# control_bdr.net
KiCad netlist of a schematic drawn in EAGLE
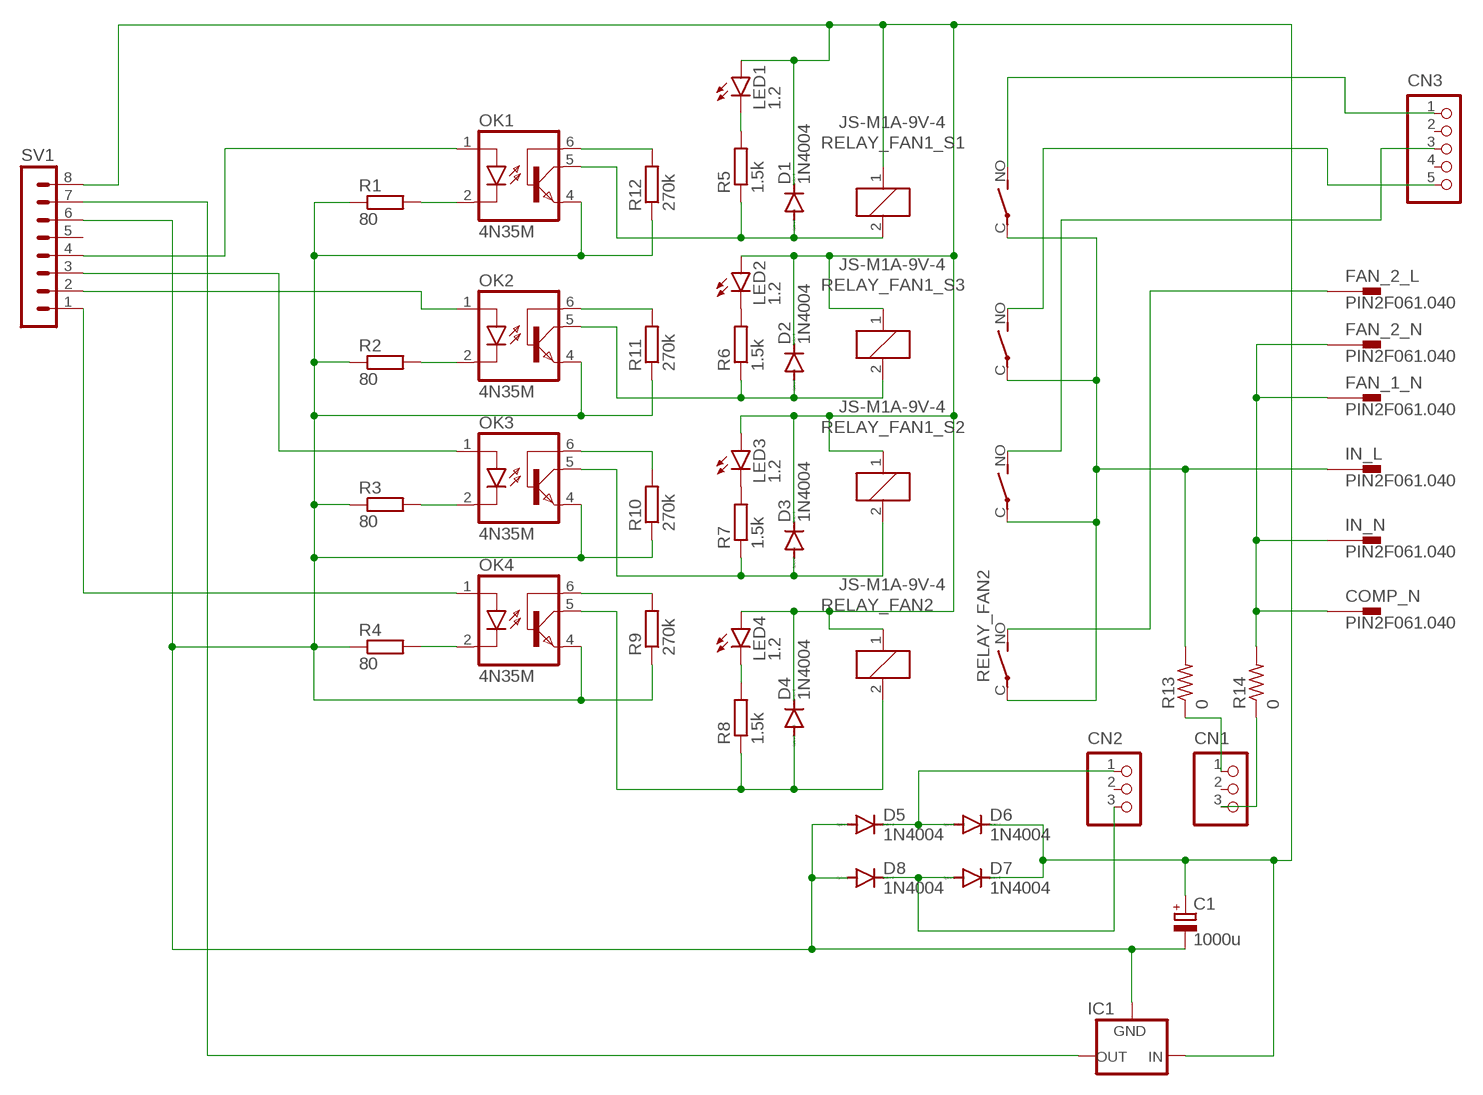
[diagram p0: schematic, sheet 1]

(export (version "E")
  (design (tool "Eeschema 10.0.6"))
  (components
    (comp (ref "C1")
      (value "1000u")
      (footprint "eagle-import:E3,5-10")
      (libsource (lib "eagle-import") (part "CPOL-EUE3.5-10"))
    )
    (comp (ref "CN1")
      (value "B3P-VH")
      (footprint "eagle-import:B3P-VH")
      (libsource (lib "eagle-import") (part "B3P-VH"))
    )
    (comp (ref "CN2")
      (value "B3B-XASK-1")
      (footprint "eagle-import:B3B-XASK-1")
      (libsource (lib "eagle-import") (part "B3B-XASK-1"))
    )
    (comp (ref "CN3")
      (value "B5P-VH")
      (footprint "eagle-import:B5P-VH")
      (libsource (lib "eagle-import") (part "B5P-VH"))
    )
    (comp (ref "COMP_N")
      (value "PIN2F061.040")
      (footprint "eagle-import:F061.040")
      (libsource (lib "eagle-import") (part "PIN2F061.040"))
    )
    (comp (ref "D1")
      (value "1N4004")
      (footprint "eagle-import:DO41-10")
      (libsource (lib "eagle-import") (part "1N4004"))
    )
    (comp (ref "D2")
      (value "1N4004")
      (footprint "eagle-import:DO41-10")
      (libsource (lib "eagle-import") (part "1N4004"))
    )
    (comp (ref "D3")
      (value "1N4004")
      (footprint "eagle-import:DO41-10")
      (libsource (lib "eagle-import") (part "1N4004"))
    )
    (comp (ref "D4")
      (value "1N4004")
      (footprint "eagle-import:DO41-10")
      (libsource (lib "eagle-import") (part "1N4004"))
    )
    (comp (ref "D5")
      (value "1N4004")
      (footprint "eagle-import:DO41-10")
      (libsource (lib "eagle-import") (part "1N4004"))
    )
    (comp (ref "D6")
      (value "1N4004")
      (footprint "eagle-import:DO41-10")
      (libsource (lib "eagle-import") (part "1N4004"))
    )
    (comp (ref "D7")
      (value "1N4004")
      (footprint "eagle-import:DO41-10")
      (libsource (lib "eagle-import") (part "1N4004"))
    )
    (comp (ref "D8")
      (value "1N4004")
      (footprint "eagle-import:DO41-10")
      (libsource (lib "eagle-import") (part "1N4004"))
    )
    (comp (ref "FAN_1_N")
      (value "PIN2F061.040")
      (footprint "eagle-import:F061.040")
      (libsource (lib "eagle-import") (part "PIN2F061.040"))
    )
    (comp (ref "FAN_2_L")
      (value "PIN2F061.040")
      (footprint "eagle-import:F061.040")
      (libsource (lib "eagle-import") (part "PIN2F061.040"))
    )
    (comp (ref "FAN_2_N")
      (value "PIN2F061.040")
      (footprint "eagle-import:F061.040")
      (libsource (lib "eagle-import") (part "PIN2F061.040"))
    )
    (comp (ref "IC1")
      (value "78XXL")
      (footprint "eagle-import:78XXL")
      (libsource (lib "eagle-import") (part "78XXL"))
    )
    (comp (ref "IN_L")
      (value "PIN2F061.040")
      (footprint "eagle-import:F061.040")
      (libsource (lib "eagle-import") (part "PIN2F061.040"))
    )
    (comp (ref "IN_N")
      (value "PIN2F061.040")
      (footprint "eagle-import:F061.040")
      (libsource (lib "eagle-import") (part "PIN2F061.040"))
    )
    (comp (ref "LED1")
      (value "1.2")
      (footprint "eagle-import:LED5MM")
      (libsource (lib "eagle-import") (part "LED5MM"))
    )
    (comp (ref "LED2")
      (value "1.2")
      (footprint "eagle-import:LED5MM")
      (libsource (lib "eagle-import") (part "LED5MM"))
    )
    (comp (ref "LED3")
      (value "1.2")
      (footprint "eagle-import:LED5MM")
      (libsource (lib "eagle-import") (part "LED5MM"))
    )
    (comp (ref "LED4")
      (value "1.2")
      (footprint "eagle-import:LED5MM")
      (libsource (lib "eagle-import") (part "LED5MM"))
    )
    (comp (ref "OK1")
      (value "4N35M")
      (footprint "eagle-import:DIL06")
      (fields (field (name "MPN") "4N35-M"))
      (libsource (lib "eagle-import") (part "4N?M35"))
    )
    (comp (ref "OK2")
      (value "4N35M")
      (footprint "eagle-import:DIL06")
      (fields (field (name "MPN") "4N35-M"))
      (libsource (lib "eagle-import") (part "4N?M35"))
    )
    (comp (ref "OK3")
      (value "4N35M")
      (footprint "eagle-import:DIL06")
      (fields (field (name "MPN") "4N35-M"))
      (libsource (lib "eagle-import") (part "4N?M35"))
    )
    (comp (ref "OK4")
      (value "4N35M")
      (footprint "eagle-import:DIL06")
      (fields (field (name "MPN") "4N35-M"))
      (libsource (lib "eagle-import") (part "4N?M35"))
    )
    (comp (ref "R1")
      (value "80")
      (footprint "eagle-import:0204_7")
      (libsource (lib "eagle-import") (part "R-EU_0204/7"))
    )
    (comp (ref "R2")
      (value "80")
      (footprint "eagle-import:0204_7")
      (libsource (lib "eagle-import") (part "R-EU_0204/7"))
    )
    (comp (ref "R3")
      (value "80")
      (footprint "eagle-import:0204_7")
      (libsource (lib "eagle-import") (part "R-EU_0204/7"))
    )
    (comp (ref "R4")
      (value "80")
      (footprint "eagle-import:0204_7")
      (libsource (lib "eagle-import") (part "R-EU_0204/7"))
    )
    (comp (ref "R5")
      (value "1.5k")
      (footprint "eagle-import:0204_7")
      (libsource (lib "eagle-import") (part "R-EU_0204/7"))
    )
    (comp (ref "R6")
      (value "1.5k")
      (footprint "eagle-import:0204_7")
      (libsource (lib "eagle-import") (part "R-EU_0204/7"))
    )
    (comp (ref "R7")
      (value "1.5k")
      (footprint "eagle-import:0204_7")
      (libsource (lib "eagle-import") (part "R-EU_0204/7"))
    )
    (comp (ref "R8")
      (value "1.5k")
      (footprint "eagle-import:0204_7")
      (libsource (lib "eagle-import") (part "R-EU_0204/7"))
    )
    (comp (ref "R9")
      (value "270k")
      (footprint "eagle-import:0204_7")
      (libsource (lib "eagle-import") (part "R-EU_0204/7"))
    )
    (comp (ref "R10")
      (value "270k")
      (footprint "eagle-import:0204_7")
      (libsource (lib "eagle-import") (part "R-EU_0204/7"))
    )
    (comp (ref "R11")
      (value "270k")
      (footprint "eagle-import:0204_7")
      (libsource (lib "eagle-import") (part "R-EU_0204/7"))
    )
    (comp (ref "R12")
      (value "270k")
      (footprint "eagle-import:0204_7")
      (libsource (lib "eagle-import") (part "R-EU_0204/7"))
    )
    (comp (ref "R13")
      (value "0")
      (footprint "eagle-import:0204V")
      (libsource (lib "eagle-import") (part "R-US_0204/2V"))
    )
    (comp (ref "R14")
      (value "0")
      (footprint "eagle-import:0204V")
      (libsource (lib "eagle-import") (part "R-US_0204/2V"))
    )
    (comp (ref "RELAY_FAN1_S1")
      (value "JS-M1A-9V-4")
      (footprint "eagle-import:JS-M1A")
      (libsource (lib "eagle-import") (part "JS-M1A-9V-4"))
    )
    (comp (ref "RELAY_FAN1_S2")
      (value "JS-M1A-9V-4")
      (footprint "eagle-import:JS-M1A")
      (libsource (lib "eagle-import") (part "JS-M1A-9V-4"))
    )
    (comp (ref "RELAY_FAN1_S3")
      (value "JS-M1A-9V-4")
      (footprint "eagle-import:JS-M1A")
      (libsource (lib "eagle-import") (part "JS-M1A-9V-4"))
    )
    (comp (ref "RELAY_FAN2")
      (value "JS-M1A-9V-4")
      (footprint "eagle-import:JS-M1A")
      (libsource (lib "eagle-import") (part "JS-M1A-9V-4"))
    )
    (comp (ref "SV1")
      (value "MA08-1")
      (footprint "eagle-import:MA08-1")
      (libsource (lib "eagle-import") (part "MA08-1"))
    )
  )
  (nets
    (net (code "1") (name "Net-(C1-Pad+)") (class "Default")
      (node (ref "C1") (pin "+") (pinfunction "+_+") (pintype "passive"))
      (node (ref "D1") (pin "C") (pinfunction "C_C") (pintype "passive"))
      (node (ref "D2") (pin "C") (pinfunction "C_C") (pintype "passive"))
      (node (ref "D3") (pin "C") (pinfunction "C_C") (pintype "passive"))
      (node (ref "D4") (pin "C") (pinfunction "C_C") (pintype "passive"))
      (node (ref "D6") (pin "C") (pinfunction "C_C") (pintype "passive"))
      (node (ref "D7") (pin "C") (pinfunction "C_C") (pintype "passive"))
      (node (ref "IC1") (pin "IN") (pinfunction "IN_IN") (pintype "input"))
      (node (ref "LED1") (pin "A") (pinfunction "A_A") (pintype "passive"))
      (node (ref "LED2") (pin "A") (pinfunction "A_A") (pintype "passive"))
      (node (ref "LED3") (pin "A") (pinfunction "A_A") (pintype "passive"))
      (node (ref "LED4") (pin "A") (pinfunction "A_A") (pintype "passive"))
      (node (ref "RELAY_FAN1_S1") (pin "1") (pinfunction "1_1") (pintype "passive"))
      (node (ref "RELAY_FAN1_S2") (pin "1") (pinfunction "1_1") (pintype "passive"))
      (node (ref "RELAY_FAN1_S3") (pin "1") (pinfunction "1_1") (pintype "passive"))
      (node (ref "RELAY_FAN2") (pin "1") (pinfunction "1_1") (pintype "passive"))
      (node (ref "SV1") (pin "8") (pinfunction "8_8") (pintype "passive"))
    )
    (net (code "2") (name "Net-(CN1-Pad1)") (class "Default")
      (node (ref "CN1") (pin "1") (pinfunction "1_1") (pintype "passive"))
      (node (ref "R13") (pin "1") (pinfunction "1_1") (pintype "passive"))
    )
    (net (code "3") (name "Net-(CN1-Pad3)") (class "Default")
      (node (ref "CN1") (pin "3") (pinfunction "3_3") (pintype "passive"))
      (node (ref "R14") (pin "1") (pinfunction "1_1") (pintype "passive"))
    )
    (net (code "4") (name "Net-(CN2-Pad1)") (class "Default")
      (node (ref "CN2") (pin "1") (pinfunction "1_1") (pintype "passive"))
      (node (ref "D5") (pin "C") (pinfunction "C_C") (pintype "passive"))
      (node (ref "D6") (pin "A") (pinfunction "A_A") (pintype "passive"))
    )
    (net (code "5") (name "Net-(CN2-Pad3)") (class "Default")
      (node (ref "CN2") (pin "3") (pinfunction "3_3") (pintype "passive"))
      (node (ref "D7") (pin "A") (pinfunction "A_A") (pintype "passive"))
      (node (ref "D8") (pin "C") (pinfunction "C_C") (pintype "passive"))
    )
    (net (code "6") (name "Net-(COMP_N-1-PadA1)") (class "Default")
      (node (ref "COMP_N") (pin "A1") (pinfunction "1_A1") (pintype "passive"))
      (node (ref "COMP_N") (pin "A2") (pinfunction "1_A2") (pintype "passive"))
      (node (ref "FAN_1_N") (pin "A1") (pinfunction "1_A1") (pintype "passive"))
      (node (ref "FAN_1_N") (pin "A2") (pinfunction "1_A2") (pintype "passive"))
      (node (ref "FAN_2_N") (pin "A1") (pinfunction "1_A1") (pintype "passive"))
      (node (ref "FAN_2_N") (pin "A2") (pinfunction "1_A2") (pintype "passive"))
      (node (ref "IN_N") (pin "A1") (pinfunction "1_A1") (pintype "passive"))
      (node (ref "IN_N") (pin "A2") (pinfunction "1_A2") (pintype "passive"))
      (node (ref "R14") (pin "2") (pinfunction "2_2") (pintype "passive"))
    )
    (net (code "7") (name "Net-(IC1-PadOUT)") (class "Default")
      (node (ref "IC1") (pin "OUT") (pinfunction "OUT_OUT") (pintype "passive"))
      (node (ref "SV1") (pin "7") (pinfunction "7_7") (pintype "passive"))
    )
    (net (code "8") (name "Net-(LED1-C)") (class "Default")
      (node (ref "LED1") (pin "K") (pinfunction "C_K") (pintype "passive"))
      (node (ref "R5") (pin "2") (pinfunction "2_2") (pintype "passive"))
    )
    (net (code "9") (name "Net-(LED2-C)") (class "Default")
      (node (ref "LED2") (pin "K") (pinfunction "C_K") (pintype "passive"))
      (node (ref "R6") (pin "2") (pinfunction "2_2") (pintype "passive"))
    )
    (net (code "10") (name "Net-(LED3-C)") (class "Default")
      (node (ref "LED3") (pin "K") (pinfunction "C_K") (pintype "passive"))
      (node (ref "R7") (pin "2") (pinfunction "2_2") (pintype "passive"))
    )
    (net (code "11") (name "Net-(LED4-C)") (class "Default")
      (node (ref "LED4") (pin "K") (pinfunction "C_K") (pintype "passive"))
      (node (ref "R8") (pin "2") (pinfunction "2_2") (pintype "passive"))
    )
    (net (code "12") (name "Net-(OK1-A)") (class "Default")
      (node (ref "OK1") (pin "1") (pinfunction "A_1") (pintype "passive"))
      (node (ref "SV1") (pin "4") (pinfunction "4_4") (pintype "passive"))
    )
    (net (code "13") (name "Net-(OK1-BAS)") (class "Default")
      (node (ref "OK1") (pin "6") (pinfunction "BAS_6") (pintype "passive"))
      (node (ref "R12") (pin "2") (pinfunction "2_2") (pintype "passive"))
    )
    (net (code "14") (name "Net-(OK1-C)") (class "Default")
      (node (ref "OK1") (pin "2") (pinfunction "C_2") (pintype "passive"))
      (node (ref "R1") (pin "2") (pinfunction "2_2") (pintype "passive"))
    )
    (net (code "15") (name "Net-(OK1-COL)") (class "Default")
      (node (ref "D1") (pin "A") (pinfunction "A_A") (pintype "passive"))
      (node (ref "OK1") (pin "5") (pinfunction "COL_5") (pintype "passive"))
      (node (ref "R5") (pin "1") (pinfunction "1_1") (pintype "passive"))
      (node (ref "RELAY_FAN1_S1") (pin "2") (pinfunction "2_2") (pintype "passive"))
    )
    (net (code "16") (name "Net-(OK1-EMI)") (class "Default")
      (node (ref "C1") (pin "-") (pinfunction "-_-") (pintype "passive"))
      (node (ref "D5") (pin "A") (pinfunction "A_A") (pintype "passive"))
      (node (ref "D8") (pin "A") (pinfunction "A_A") (pintype "passive"))
      (node (ref "IC1") (pin "GND") (pinfunction "GND_GND") (pintype "input"))
      (node (ref "OK1") (pin "4") (pinfunction "EMI_4") (pintype "passive"))
      (node (ref "OK2") (pin "4") (pinfunction "EMI_4") (pintype "passive"))
      (node (ref "OK3") (pin "4") (pinfunction "EMI_4") (pintype "passive"))
      (node (ref "OK4") (pin "4") (pinfunction "EMI_4") (pintype "passive"))
      (node (ref "R1") (pin "1") (pinfunction "1_1") (pintype "passive"))
      (node (ref "R10") (pin "1") (pinfunction "1_1") (pintype "passive"))
      (node (ref "R11") (pin "1") (pinfunction "1_1") (pintype "passive"))
      (node (ref "R12") (pin "1") (pinfunction "1_1") (pintype "passive"))
      (node (ref "R2") (pin "1") (pinfunction "1_1") (pintype "passive"))
      (node (ref "R3") (pin "1") (pinfunction "1_1") (pintype "passive"))
      (node (ref "R4") (pin "1") (pinfunction "1_1") (pintype "passive"))
      (node (ref "R9") (pin "1") (pinfunction "1_1") (pintype "passive"))
      (node (ref "SV1") (pin "6") (pinfunction "6_6") (pintype "passive"))
    )
    (net (code "17") (name "Net-(OK2-A)") (class "Default")
      (node (ref "OK2") (pin "1") (pinfunction "A_1") (pintype "passive"))
      (node (ref "SV1") (pin "2") (pinfunction "2_2") (pintype "passive"))
    )
    (net (code "18") (name "Net-(OK2-BAS)") (class "Default")
      (node (ref "OK2") (pin "6") (pinfunction "BAS_6") (pintype "passive"))
      (node (ref "R11") (pin "2") (pinfunction "2_2") (pintype "passive"))
    )
    (net (code "19") (name "Net-(OK2-C)") (class "Default")
      (node (ref "OK2") (pin "2") (pinfunction "C_2") (pintype "passive"))
      (node (ref "R2") (pin "2") (pinfunction "2_2") (pintype "passive"))
    )
    (net (code "20") (name "Net-(OK2-COL)") (class "Default")
      (node (ref "D2") (pin "A") (pinfunction "A_A") (pintype "passive"))
      (node (ref "OK2") (pin "5") (pinfunction "COL_5") (pintype "passive"))
      (node (ref "R6") (pin "1") (pinfunction "1_1") (pintype "passive"))
      (node (ref "RELAY_FAN1_S3") (pin "2") (pinfunction "2_2") (pintype "passive"))
    )
    (net (code "21") (name "Net-(OK3-A)") (class "Default")
      (node (ref "OK3") (pin "1") (pinfunction "A_1") (pintype "passive"))
      (node (ref "SV1") (pin "3") (pinfunction "3_3") (pintype "passive"))
    )
    (net (code "22") (name "Net-(OK3-BAS)") (class "Default")
      (node (ref "OK3") (pin "6") (pinfunction "BAS_6") (pintype "passive"))
      (node (ref "R10") (pin "2") (pinfunction "2_2") (pintype "passive"))
    )
    (net (code "23") (name "Net-(OK3-C)") (class "Default")
      (node (ref "OK3") (pin "2") (pinfunction "C_2") (pintype "passive"))
      (node (ref "R3") (pin "2") (pinfunction "2_2") (pintype "passive"))
    )
    (net (code "24") (name "Net-(OK3-COL)") (class "Default")
      (node (ref "D3") (pin "A") (pinfunction "A_A") (pintype "passive"))
      (node (ref "OK3") (pin "5") (pinfunction "COL_5") (pintype "passive"))
      (node (ref "R7") (pin "1") (pinfunction "1_1") (pintype "passive"))
      (node (ref "RELAY_FAN1_S2") (pin "2") (pinfunction "2_2") (pintype "passive"))
    )
    (net (code "25") (name "Net-(OK4-A)") (class "Default")
      (node (ref "OK4") (pin "1") (pinfunction "A_1") (pintype "passive"))
      (node (ref "SV1") (pin "1") (pinfunction "1_1") (pintype "passive"))
    )
    (net (code "26") (name "Net-(OK4-BAS)") (class "Default")
      (node (ref "OK4") (pin "6") (pinfunction "BAS_6") (pintype "passive"))
      (node (ref "R9") (pin "2") (pinfunction "2_2") (pintype "passive"))
    )
    (net (code "27") (name "Net-(OK4-C)") (class "Default")
      (node (ref "OK4") (pin "2") (pinfunction "C_2") (pintype "passive"))
      (node (ref "R4") (pin "2") (pinfunction "2_2") (pintype "passive"))
    )
    (net (code "28") (name "Net-(OK4-COL)") (class "Default")
      (node (ref "D4") (pin "A") (pinfunction "A_A") (pintype "passive"))
      (node (ref "OK4") (pin "5") (pinfunction "COL_5") (pintype "passive"))
      (node (ref "R8") (pin "1") (pinfunction "1_1") (pintype "passive"))
      (node (ref "RELAY_FAN2") (pin "2") (pinfunction "2_2") (pintype "passive"))
    )
    (net (code "29") (name "Net-(RELAY_FAN1_S1B-P)") (class "Default")
      (node (ref "IN_L") (pin "A1") (pinfunction "1_A1") (pintype "passive"))
      (node (ref "IN_L") (pin "A2") (pinfunction "1_A2") (pintype "passive"))
      (node (ref "R13") (pin "2") (pinfunction "2_2") (pintype "passive"))
      (node (ref "RELAY_FAN1_S1") (pin "C") (pinfunction "P_C") (pintype "passive"))
      (node (ref "RELAY_FAN1_S2") (pin "C") (pinfunction "P_C") (pintype "passive"))
      (node (ref "RELAY_FAN1_S3") (pin "C") (pinfunction "P_C") (pintype "passive"))
      (node (ref "RELAY_FAN2") (pin "C") (pinfunction "P_C") (pintype "passive"))
    )
    (net (code "30") (name "Net-(RELAY_FAN1_S1B-S)") (class "Default")
      (node (ref "CN3") (pin "1") (pinfunction "1_1") (pintype "passive"))
      (node (ref "RELAY_FAN1_S1") (pin "NO") (pinfunction "S_NO") (pintype "passive"))
    )
    (net (code "31") (name "Net-(RELAY_FAN1_S2B-S)") (class "Default")
      (node (ref "CN3") (pin "3") (pinfunction "3_3") (pintype "passive"))
      (node (ref "RELAY_FAN1_S2") (pin "NO") (pinfunction "S_NO") (pintype "passive"))
    )
    (net (code "32") (name "Net-(RELAY_FAN1_S3B-S)") (class "Default")
      (node (ref "CN3") (pin "5") (pinfunction "5_5") (pintype "passive"))
      (node (ref "RELAY_FAN1_S3") (pin "NO") (pinfunction "S_NO") (pintype "passive"))
    )
    (net (code "33") (name "Net-(RELAY_FAN2B-S)") (class "Default")
      (node (ref "FAN_2_L") (pin "A1") (pinfunction "1_A1") (pintype "passive"))
      (node (ref "FAN_2_L") (pin "A2") (pinfunction "1_A2") (pintype "passive"))
      (node (ref "RELAY_FAN2") (pin "NO") (pinfunction "S_NO") (pintype "passive"))
    )
    (net (code "34") (name "unconnected-(CN1-Pad2)") (class "Default")
      (node (ref "CN1") (pin "2") (pinfunction "2_2") (pintype "passive"))
    )
    (net (code "35") (name "unconnected-(CN2-Pad2)") (class "Default")
      (node (ref "CN2") (pin "2") (pinfunction "2_2") (pintype "passive"))
    )
    (net (code "36") (name "unconnected-(CN3-Pad2)") (class "Default")
      (node (ref "CN3") (pin "2") (pinfunction "2_2") (pintype "passive"))
    )
    (net (code "37") (name "unconnected-(CN3-Pad4)") (class "Default")
      (node (ref "CN3") (pin "4") (pinfunction "4_4") (pintype "passive"))
    )
    (net (code "38") (name "unconnected-(SV1-Pad5)") (class "Default")
      (node (ref "SV1") (pin "5") (pinfunction "5_5") (pintype "passive"))
    )
  )
)
